# Mini_Arduino_5mm.net
KiCad netlist of a schematic drawn in EAGLE
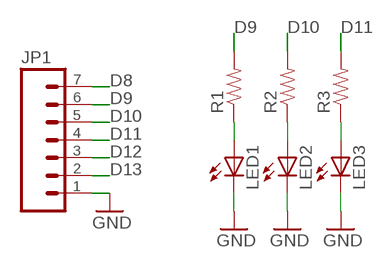
[diagram p0: schematic, sheet 1]

(export (version "E")
  (design (tool "Eeschema 10.0.6"))
  (components
    (comp (ref "JP1")
      (value "M07")
      (footprint "eagle-import:1X07")
      (libsource (lib "eagle-import") (part "M07"))
    )
    (comp (ref "LED1")
      (value "LED5MM")
      (footprint "eagle-import:LED5MM")
      (libsource (lib "eagle-import") (part "LED5MM"))
    )
    (comp (ref "LED2")
      (value "LED5MM")
      (footprint "eagle-import:LED5MM")
      (libsource (lib "eagle-import") (part "LED5MM"))
    )
    (comp (ref "LED3")
      (value "LED5MM")
      (footprint "eagle-import:LED5MM")
      (libsource (lib "eagle-import") (part "LED5MM"))
    )
    (comp (ref "R1")
      (value "RESISTORAXIAL-0.3")
      (footprint "eagle-import:AXIAL-0.3")
      (libsource (lib "eagle-import") (part "RESISTORAXIAL-0.3"))
    )
    (comp (ref "R2")
      (value "RESISTORAXIAL-0.3")
      (footprint "eagle-import:AXIAL-0.3")
      (libsource (lib "eagle-import") (part "RESISTORAXIAL-0.3"))
    )
    (comp (ref "R3")
      (value "RESISTORAXIAL-0.3")
      (footprint "eagle-import:AXIAL-0.3")
      (libsource (lib "eagle-import") (part "RESISTORAXIAL-0.3"))
    )
  )
  (nets
    (net (code "1") (name "/D8") (class "Default")
      (node (ref "JP1") (pin "7") (pinfunction "7_7") (pintype "passive"))
    )
    (net (code "2") (name "/D9") (class "Default")
      (node (ref "JP1") (pin "6") (pinfunction "6_6") (pintype "passive"))
      (node (ref "R1") (pin "P$2") (pinfunction "2_P$2") (pintype "passive"))
    )
    (net (code "3") (name "/D10") (class "Default")
      (node (ref "JP1") (pin "5") (pinfunction "5_5") (pintype "passive"))
      (node (ref "R2") (pin "P$2") (pinfunction "2_P$2") (pintype "passive"))
    )
    (net (code "4") (name "/D11") (class "Default")
      (node (ref "JP1") (pin "4") (pinfunction "4_4") (pintype "passive"))
      (node (ref "R3") (pin "P$2") (pinfunction "2_P$2") (pintype "passive"))
    )
    (net (code "5") (name "/D12") (class "Default")
      (node (ref "JP1") (pin "3") (pinfunction "3_3") (pintype "passive"))
    )
    (net (code "6") (name "/D13") (class "Default")
      (node (ref "JP1") (pin "2") (pinfunction "2_2") (pintype "passive"))
    )
    (net (code "7") (name "GND") (class "Default")
      (node (ref "JP1") (pin "1") (pinfunction "1_1") (pintype "passive"))
      (node (ref "LED1") (pin "K") (pinfunction "C_K") (pintype "passive"))
      (node (ref "LED2") (pin "K") (pinfunction "C_K") (pintype "passive"))
      (node (ref "LED3") (pin "K") (pinfunction "C_K") (pintype "passive"))
    )
    (net (code "8") (name "Net-(R1-1)") (class "Default")
      (node (ref "LED1") (pin "A") (pinfunction "A_A") (pintype "passive"))
      (node (ref "R1") (pin "P$1") (pinfunction "1_P$1") (pintype "passive"))
    )
    (net (code "9") (name "Net-(R2-1)") (class "Default")
      (node (ref "LED2") (pin "A") (pinfunction "A_A") (pintype "passive"))
      (node (ref "R2") (pin "P$1") (pinfunction "1_P$1") (pintype "passive"))
    )
    (net (code "10") (name "Net-(R3-1)") (class "Default")
      (node (ref "LED3") (pin "A") (pinfunction "A_A") (pintype "passive"))
      (node (ref "R3") (pin "P$1") (pinfunction "1_P$1") (pintype "passive"))
    )
  )
)
